# Serial_ID_EEPROM.net
KiCad netlist of a schematic drawn in Altium Designer
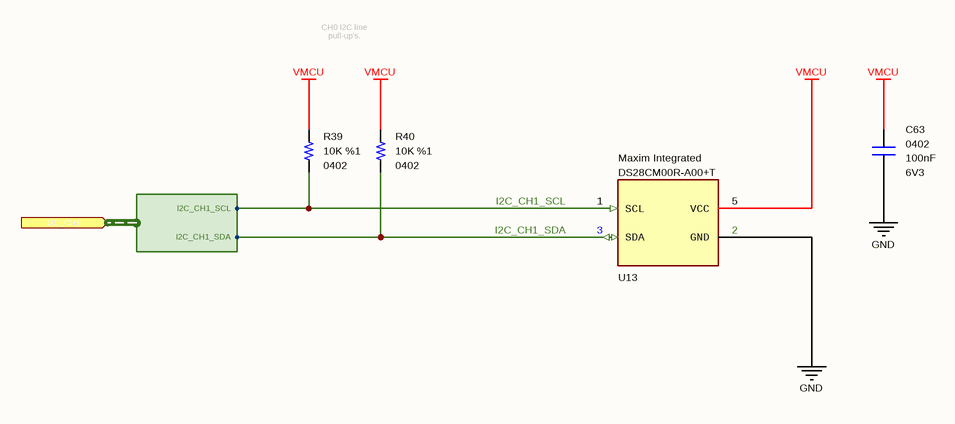
[diagram p0: Serial ID EEPROM.SchDoc]

(export (version "E")
  (design (tool "Eeschema 10.0.6"))
  (components
    (comp (ref "C63")
      (value "100nF")
      (footprint "CAPACITOR_0402")
      (description "Capacitor - 100nF [0402-6V3] (Ceramic)")
      (fields
        (field (name "TOLERANCE") "%10")
        (field (name "CASE") "0402")
        (field (name "VOLTAGE") "6V3")
        (field (name "MANUFACTURER PART NUMBER") "04026D104KAT4A")
      )
      (libsource (lib "Ovoo_Library") (part "Capacitor - 100nF [0402-6V3]"))
    )
    (comp (ref "R39")
      (value "10K")
      (footprint "RESISTOR_0402")
      (description "Thick Film Resistors - SMD 1/16 W 10 Kohms 1%")
      (fields
        (field (name "TOLERANCE") "%1")
        (field (name "CASE") "0402")
        (field (name "MANUFACTURER PART NUMBER") "CRCW040210K0FKED")
        (field (name "MOUSER PART NUMBER") "71-CRCW0402-10K-E3")
      )
      (libsource (lib "Ovoo_Library") (part "Resistor - 10K"))
    )
    (comp (ref "R40")
      (value "10K")
      (footprint "RESISTOR_0402")
      (description "Thick Film Resistors - SMD 1/16 W 10 Kohms 1%")
      (fields
        (field (name "TOLERANCE") "%1")
        (field (name "CASE") "0402")
        (field (name "MANUFACTURER PART NUMBER") "CRCW040210K0FKED")
        (field (name "MOUSER PART NUMBER") "71-CRCW0402-10K-E3")
      )
      (libsource (lib "Ovoo_Library") (part "Resistor - 10K"))
    )
    (comp (ref "U13")
      (value "Security ICs / Authentication ICs")
      (footprint "SOT-23-5")
      (description "Security ICs / Authentication ICs I C/SMBus Silicon Serial Number")
      (fields
        (field (name "MOUSER PART NUMBER") "700-DS28CM00R-A00T")
        (field (name "MANUFACTURER PART NUMBER") "DS28CM00R-A00+T")
        (field (name "MANUFACTURER NAME") "Maxim Integrated")
      )
      (libsource (lib "Ovoo_Library") (part "IC - DS28CM00R-A00+T"))
    )
  )
  (nets
    (net (code "2") (name "/I2C_CH1_SCL") (class "Default")
      (node (ref "R39") (pin "1") (pinfunction "1_1") (pintype "passive"))
      (node (ref "U13") (pin "1") (pinfunction "SCL_1") (pintype "input"))
    )
    (net (code "3") (name "/I2C_CH1_SDA") (class "Default")
      (node (ref "R40") (pin "1") (pinfunction "1_1") (pintype "passive"))
      (node (ref "U13") (pin "3") (pinfunction "SDA_3") (pintype "bidirectional"))
    )
    (net (code "5") (name "GND") (class "Default")
      (node (ref "C63") (pin "1") (pinfunction "1_1") (pintype "passive"))
      (node (ref "U13") (pin "2") (pinfunction "GND_2") (pintype "passive"))
    )
    (net (code "6") (name "VMCU") (class "Default")
      (node (ref "C63") (pin "2") (pinfunction "2_2") (pintype "passive"))
      (node (ref "R39") (pin "2") (pinfunction "2_2") (pintype "passive"))
      (node (ref "R40") (pin "2") (pinfunction "2_2") (pintype "passive"))
      (node (ref "U13") (pin "5") (pinfunction "VCC_5") (pintype "power_in"))
    )
    (net (code "7") (name "unconnected-(U13-NC-Pad4)") (class "Default")
      (node (ref "U13") (pin "4") (pinfunction "NC_4") (pintype "passive"))
    )
  )
)
